# Schem.net
KiCad netlist of a schematic drawn in Altium Designer
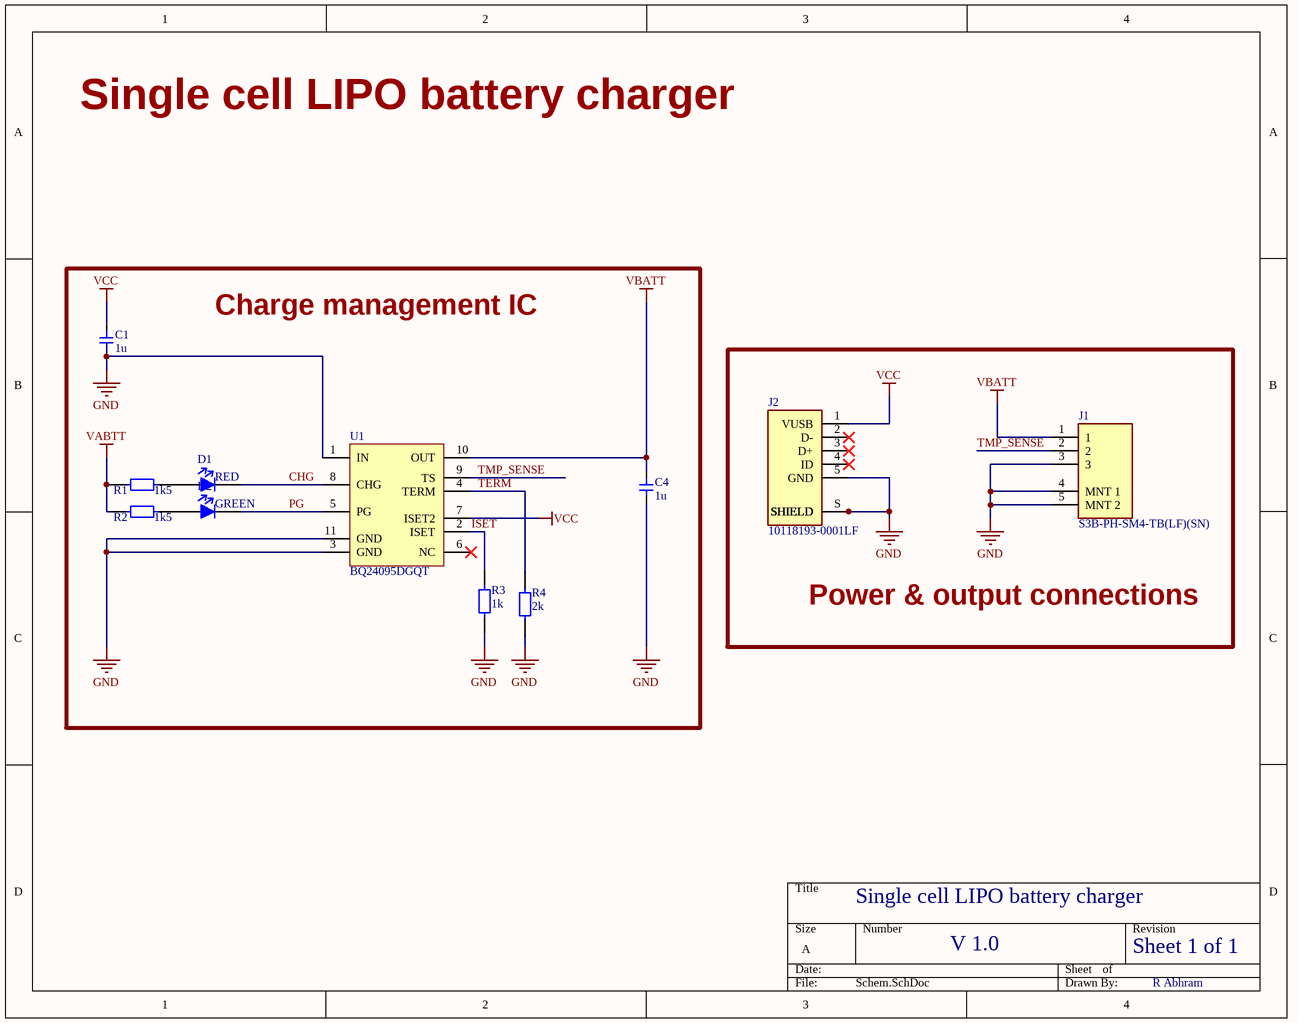
[diagram p0: Schem.SchDoc]

(export (version "E")
  (design (tool "Eeschema 10.0.6"))
  (components
    (comp (ref "C1")
      (value "1u")
      (footprint "1U_0402_CAP")
      (description "CAP CER 1UF 10V X5R 0402")
      (fields
        (field (name "MANUFACTURER") "Yageo")
        (field (name "MANUFACTURER PART NUMBER") "CC0402KRX5R6BB105")
      )
      (libsource (lib "Schlib") (part "CC0402KRX5R6BB105"))
    )
    (comp (ref "C4")
      (value "1u")
      (footprint "1U_0402_CAP")
      (description "CAP CER 1UF 10V X5R 0402")
      (fields
        (field (name "MANUFACTURER") "Yageo")
        (field (name "MANUFACTURER PART NUMBER") "CC0402KRX5R6BB105")
      )
      (libsource (lib "Schlib") (part "CC0402KRX5R6BB105"))
    )
    (comp (ref "D1")
      (value "RED")
      (footprint "RED_LED")
      (description "LED RED CLEAR 0402 SMD")
      (fields
        (field (name "MANUFACTURER") "Wurth Electronics")
        (field (name "MANUFACTURER PART NUMBER") "150040RS73240")
      )
      (libsource (lib "Schlib") (part "150040RS73240"))
    )
    (comp (ref "D2")
      (value "GREEN")
      (footprint "GREEN_LED")
      (description "LED GREEN CLEAR 0402 SMD")
      (fields
        (field (name "MANUFACTURER") "Wurth Electronics")
        (field (name "MANUFACTURER PART NUMBER") "150040VS73240")
      )
      (libsource (lib "Schlib") (part "150040VS73240"))
    )
    (comp (ref "J1")
      (value "S3B-PH-SM4-TB(LF)(SN)")
      (footprint "JST_3POS")
      (description "Connector Header, PH Series, 3 Position, Side Entry, 2.00mm, Solder, Surface Mount, Natural.")
      (fields (field (name "MANUFACTURER") "JST"))
      (libsource (lib "Schlib") (part "S3B-PH-SM4-TB(LF)(SN)"))
    )
    (comp (ref "J2")
      (value "10118193-0001LF")
      (footprint "USB_PWR_CTR")
      (description "CONN RCPT USB2.0 MICRO B SMD R/A")
      (fields (field (name "MANUFACTURER") "Amphenol ICC / FCI"))
      (libsource (lib "Schlib") (part "10118193-0001LF"))
    )
    (comp (ref "R1")
      (value "1k5")
      (footprint "1K5_0402_RES")
      (description "RES SMD 1.5K OHM 0.1% 1/16W 0402")
      (fields
        (field (name "MANUFACTURER") "Yageo")
        (field (name "MANUFACTURER PART NUMBER") "RT0402BRD071K5L")
      )
      (libsource (lib "Schlib") (part "RT0402BRD071K5L"))
    )
    (comp (ref "R2")
      (value "1k5")
      (footprint "1K5_0402_RES")
      (description "RES SMD 1.5K OHM 0.1% 1/16W 0402")
      (fields
        (field (name "MANUFACTURER") "Yageo")
        (field (name "MANUFACTURER PART NUMBER") "RT0402BRD071K5L")
      )
      (libsource (lib "Schlib") (part "RT0402BRD071K5L"))
    )
    (comp (ref "R3")
      (value "1k")
      (footprint "1k_0402_RES")
      (description "RES 1K OHM 5% 1/16W 0402")
      (fields
        (field (name "MANUFACTURER") "Yageo")
        (field (name "MANUFACTURER PART NUMBER") "RC0402JR-071KL")
      )
      (libsource (lib "Schlib") (part "RC0402JR-071KL"))
    )
    (comp (ref "R4")
      (value "2k")
      (footprint "2K_0402_RES")
      (description "RES 2K OHM 1% 1/16W 0402")
      (fields
        (field (name "MANUFACTURER") "Yageo")
        (field (name "MANUFACTURER PART NUMBER") "RC0402FR-072KL")
      )
      (libsource (lib "Schlib") (part "RC0402FR-072KL"))
    )
    (comp (ref "U1")
      (value "BQ24095DGQT")
      (footprint "BATT_CHARGE_IC")
      (description "IC BATT CHG LI-ION 1CELL 10MSOP")
      (fields (field (name "MANUFACTURER") "Texas Instruments"))
      (libsource (lib "Schlib") (part "BQ24095DGQT"))
    )
  )
  (nets
    (net (code "1") (name "/CHG") (class "Default")
      (node (ref "D1") (pin "2") (pinfunction "2_2") (pintype "passive"))
      (node (ref "U1") (pin "8") (pinfunction "CHG_8") (pintype "passive"))
    )
    (net (code "2") (name "/ISET") (class "Default")
      (node (ref "R3") (pin "2") (pinfunction "2_2") (pintype "passive"))
      (node (ref "U1") (pin "2") (pinfunction "ISET_2") (pintype "passive"))
    )
    (net (code "3") (name "/PG") (class "Default")
      (node (ref "D2") (pin "2") (pinfunction "2_2") (pintype "passive"))
      (node (ref "U1") (pin "5") (pinfunction "PG_5") (pintype "passive"))
    )
    (net (code "4") (name "/TERM") (class "Default")
      (node (ref "R4") (pin "2") (pinfunction "2_2") (pintype "passive"))
      (node (ref "U1") (pin "4") (pinfunction "TERM_4") (pintype "passive"))
    )
    (net (code "5") (name "/TMP_SENSE") (class "Default")
      (node (ref "J1") (pin "2") (pinfunction "2_2") (pintype "passive"))
      (node (ref "U1") (pin "9") (pinfunction "TS_9") (pintype "passive"))
    )
    (net (code "6") (name "GND") (class "Default")
      (node (ref "C1") (pin "1") (pinfunction "1_1") (pintype "passive"))
      (node (ref "C4") (pin "1") (pinfunction "1_1") (pintype "passive"))
      (node (ref "J1") (pin "3") (pinfunction "3_3") (pintype "passive"))
      (node (ref "J1") (pin "4") (pinfunction "MNT_1_4") (pintype "passive"))
      (node (ref "J1") (pin "5") (pinfunction "MNT_2_5") (pintype "passive"))
      (node (ref "J2") (pin "5") (pinfunction "GND_5") (pintype "passive"))
      (node (ref "J2") (pin "6") (pinfunction "SHIELD_6") (pintype "passive"))
      (node (ref "J2") (pin "S") (pinfunction "SHIELD_S") (pintype "passive"))
      (node (ref "R3") (pin "1") (pinfunction "1_1") (pintype "passive"))
      (node (ref "R4") (pin "1") (pinfunction "1_1") (pintype "passive"))
      (node (ref "U1") (pin "1") (pinfunction "IN_1") (pintype "passive"))
      (node (ref "U1") (pin "11") (pinfunction "GND_11") (pintype "passive"))
      (node (ref "U1") (pin "3") (pinfunction "GND_3") (pintype "passive"))
    )
    (net (code "7") (name "Net-(D1-Pad1)") (class "Default")
      (node (ref "D1") (pin "1") (pinfunction "1_1") (pintype "passive"))
      (node (ref "R1") (pin "2") (pinfunction "2_2") (pintype "passive"))
    )
    (net (code "8") (name "Net-(D2-Pad1)") (class "Default")
      (node (ref "D2") (pin "1") (pinfunction "1_1") (pintype "passive"))
      (node (ref "R2") (pin "2") (pinfunction "2_2") (pintype "passive"))
    )
    (net (code "9") (name "VABTT") (class "Default")
      (node (ref "R1") (pin "1") (pinfunction "1_1") (pintype "passive"))
      (node (ref "R2") (pin "1") (pinfunction "1_1") (pintype "passive"))
    )
    (net (code "10") (name "VBATT") (class "Default")
      (node (ref "C4") (pin "2") (pinfunction "2_2") (pintype "passive"))
      (node (ref "J1") (pin "1") (pinfunction "1_1") (pintype "passive"))
      (node (ref "U1") (pin "10") (pinfunction "OUT_10") (pintype "passive"))
    )
    (net (code "11") (name "VCC") (class "Default")
      (node (ref "C1") (pin "2") (pinfunction "2_2") (pintype "passive"))
      (node (ref "J2") (pin "1") (pinfunction "VUSB_1") (pintype "passive"))
      (node (ref "U1") (pin "7") (pinfunction "ISET2_7") (pintype "passive"))
    )
    (net (code "12") (name "unconnected-(J2-D+-Pad3)") (class "Default")
      (node (ref "J2") (pin "3") (pinfunction "D+_3") (pintype "passive+no_connect"))
    )
    (net (code "13") (name "unconnected-(J2-D--Pad2)") (class "Default")
      (node (ref "J2") (pin "2") (pinfunction "D-_2") (pintype "passive+no_connect"))
    )
    (net (code "14") (name "unconnected-(J2-ID-Pad4)") (class "Default")
      (node (ref "J2") (pin "4") (pinfunction "ID_4") (pintype "passive+no_connect"))
    )
    (net (code "15") (name "unconnected-(U1-NC-Pad6)") (class "Default")
      (node (ref "U1") (pin "6") (pinfunction "NC_6") (pintype "passive+no_connect"))
    )
  )
)
